# main.net
KiCad netlist of a schematic drawn in EAGLE
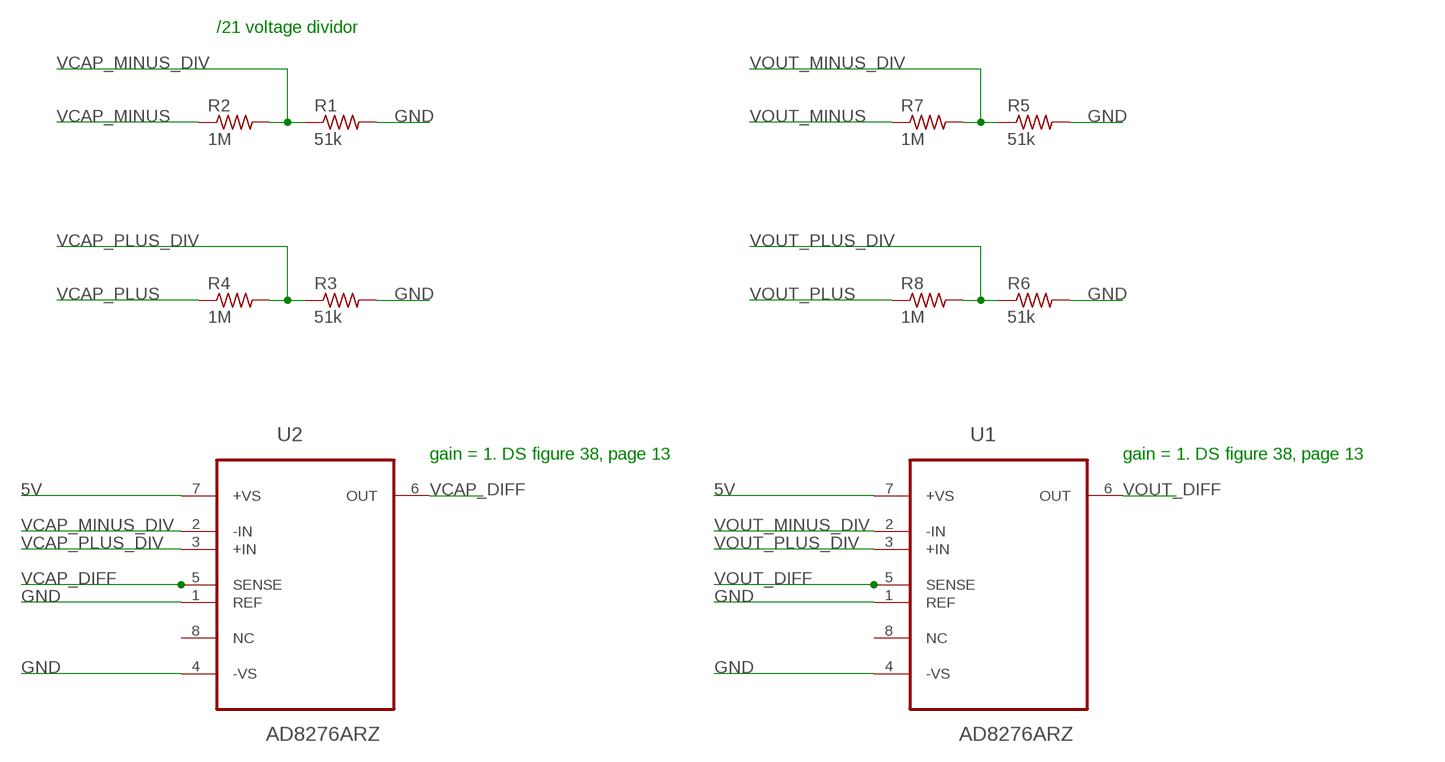
[diagram p0: schematic, sheet 1]

(export (version "E")
  (design (tool "Eeschema 10.0.6"))
  (components
    (comp (ref "R1")
      (value "51k")
      (footprint "eagle-import:R1206")
      (libsource (lib "eagle-import") (part "R-US_R1206"))
    )
    (comp (ref "R2")
      (value "1M")
      (footprint "eagle-import:R1206")
      (libsource (lib "eagle-import") (part "R-US_R1206"))
    )
    (comp (ref "R3")
      (value "51k")
      (footprint "eagle-import:R1206")
      (libsource (lib "eagle-import") (part "R-US_R1206"))
    )
    (comp (ref "R4")
      (value "1M")
      (footprint "eagle-import:R1206")
      (libsource (lib "eagle-import") (part "R-US_R1206"))
    )
    (comp (ref "R5")
      (value "51k")
      (footprint "eagle-import:R1206")
      (libsource (lib "eagle-import") (part "R-US_R1206"))
    )
    (comp (ref "R6")
      (value "51k")
      (footprint "eagle-import:R1206")
      (libsource (lib "eagle-import") (part "R-US_R1206"))
    )
    (comp (ref "R7")
      (value "1M")
      (footprint "eagle-import:R1206")
      (libsource (lib "eagle-import") (part "R-US_R1206"))
    )
    (comp (ref "R8")
      (value "1M")
      (footprint "eagle-import:R1206")
      (libsource (lib "eagle-import") (part "R-US_R1206"))
    )
    (comp (ref "U1")
      (value "AD8276ARZ")
      (footprint "eagle-import:SOIC127P600X175-8N")
      (libsource (lib "eagle-import") (part "AD8276ARZ"))
    )
    (comp (ref "U2")
      (value "AD8276ARZ")
      (footprint "eagle-import:SOIC127P600X175-8N")
      (libsource (lib "eagle-import") (part "AD8276ARZ"))
    )
  )
  (nets
    (net (code "1") (name "/5V") (class "Default")
      (node (ref "U1") (pin "7") (pinfunction "+VS_7") (pintype "power_in"))
      (node (ref "U2") (pin "7") (pinfunction "+VS_7") (pintype "power_in"))
    )
    (net (code "2") (name "/GND") (class "Default")
      (node (ref "R1") (pin "2") (pinfunction "2_2") (pintype "passive"))
      (node (ref "R3") (pin "2") (pinfunction "2_2") (pintype "passive"))
      (node (ref "R5") (pin "2") (pinfunction "2_2") (pintype "passive"))
      (node (ref "R6") (pin "2") (pinfunction "2_2") (pintype "passive"))
      (node (ref "U1") (pin "1") (pinfunction "REF_1") (pintype "input"))
      (node (ref "U1") (pin "4") (pinfunction "-VS_4") (pintype "power_in"))
      (node (ref "U2") (pin "1") (pinfunction "REF_1") (pintype "input"))
      (node (ref "U2") (pin "4") (pinfunction "-VS_4") (pintype "power_in"))
    )
    (net (code "3") (name "/VCAP_DIFF") (class "Default")
      (node (ref "U2") (pin "5") (pinfunction "SENSE_5") (pintype "passive"))
      (node (ref "U2") (pin "6") (pinfunction "OUT_6") (pintype "output"))
    )
    (net (code "4") (name "/VCAP_MINUS") (class "Default")
      (node (ref "R2") (pin "1") (pinfunction "1_1") (pintype "passive"))
    )
    (net (code "5") (name "/VCAP_MINUS_DIV") (class "Default")
      (node (ref "R1") (pin "1") (pinfunction "1_1") (pintype "passive"))
      (node (ref "R2") (pin "2") (pinfunction "2_2") (pintype "passive"))
      (node (ref "U2") (pin "2") (pinfunction "-IN_2") (pintype "input"))
    )
    (net (code "6") (name "/VCAP_PLUS") (class "Default")
      (node (ref "R4") (pin "1") (pinfunction "1_1") (pintype "passive"))
    )
    (net (code "7") (name "/VCAP_PLUS_DIV") (class "Default")
      (node (ref "R3") (pin "1") (pinfunction "1_1") (pintype "passive"))
      (node (ref "R4") (pin "2") (pinfunction "2_2") (pintype "passive"))
      (node (ref "U2") (pin "3") (pinfunction "+IN_3") (pintype "input"))
    )
    (net (code "8") (name "/VOUT_DIFF") (class "Default")
      (node (ref "U1") (pin "5") (pinfunction "SENSE_5") (pintype "passive"))
      (node (ref "U1") (pin "6") (pinfunction "OUT_6") (pintype "output"))
    )
    (net (code "9") (name "/VOUT_MINUS") (class "Default")
      (node (ref "R7") (pin "1") (pinfunction "1_1") (pintype "passive"))
    )
    (net (code "10") (name "/VOUT_MINUS_DIV") (class "Default")
      (node (ref "R5") (pin "1") (pinfunction "1_1") (pintype "passive"))
      (node (ref "R7") (pin "2") (pinfunction "2_2") (pintype "passive"))
      (node (ref "U1") (pin "2") (pinfunction "-IN_2") (pintype "input"))
    )
    (net (code "11") (name "/VOUT_PLUS") (class "Default")
      (node (ref "R8") (pin "1") (pinfunction "1_1") (pintype "passive"))
    )
    (net (code "12") (name "/VOUT_PLUS_DIV") (class "Default")
      (node (ref "R6") (pin "1") (pinfunction "1_1") (pintype "passive"))
      (node (ref "R8") (pin "2") (pinfunction "2_2") (pintype "passive"))
      (node (ref "U1") (pin "3") (pinfunction "+IN_3") (pintype "input"))
    )
    (net (code "13") (name "unconnected-(U1-NC-Pad8)") (class "Default")
      (node (ref "U1") (pin "8") (pinfunction "NC_8") (pintype "no_connect"))
    )
    (net (code "14") (name "unconnected-(U2-NC-Pad8)") (class "Default")
      (node (ref "U2") (pin "8") (pinfunction "NC_8") (pintype "no_connect"))
    )
  )
)
